# PCB_Telemetria_2020.net
KiCad netlist of a schematic drawn in EAGLE
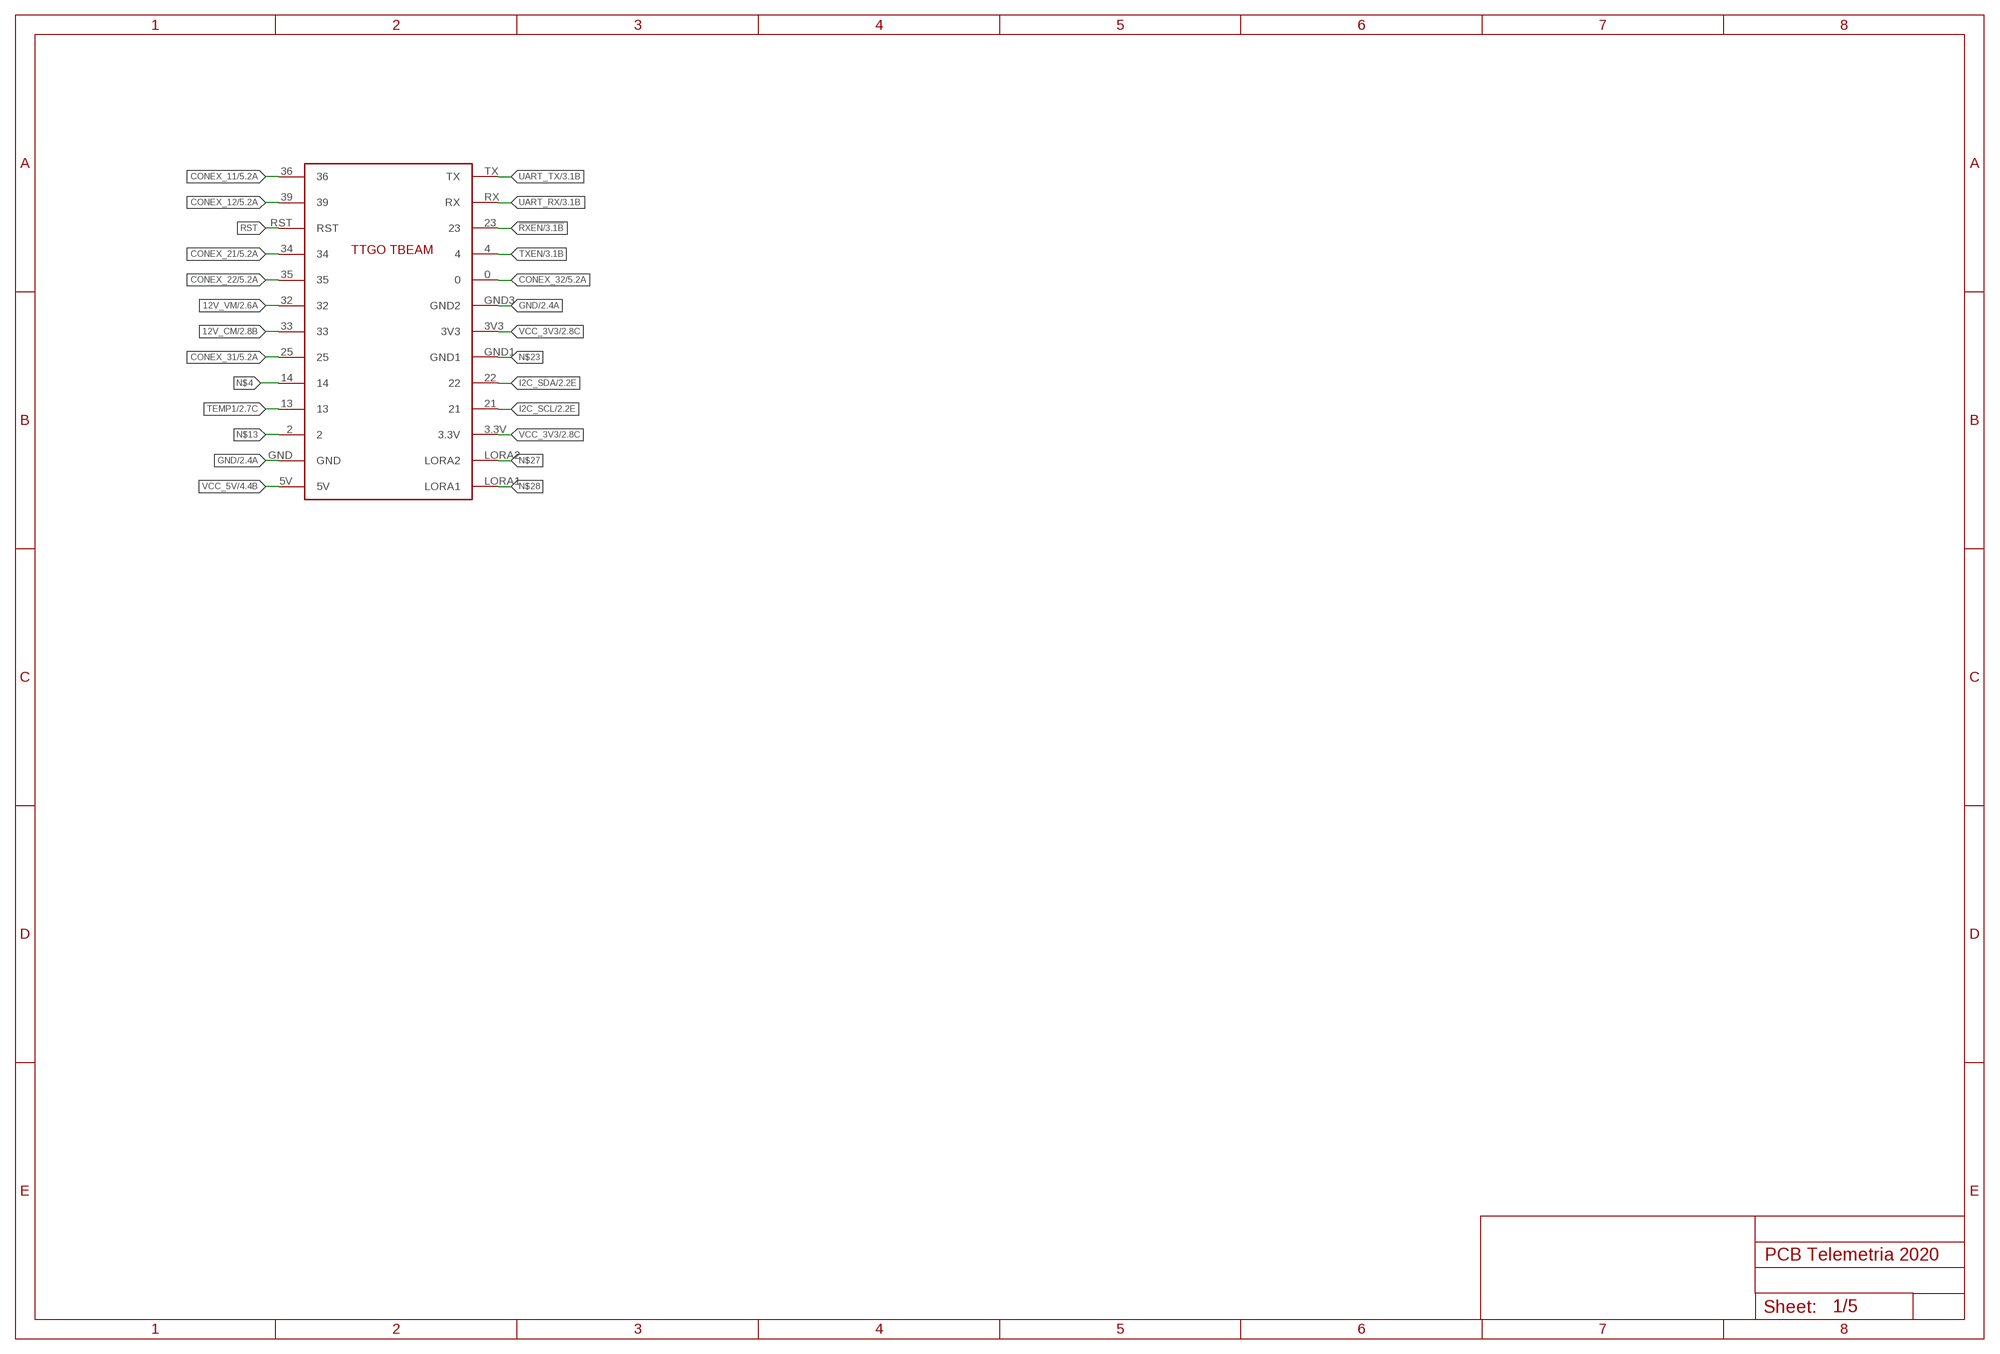
[diagram p0: schematic, sheet 1]
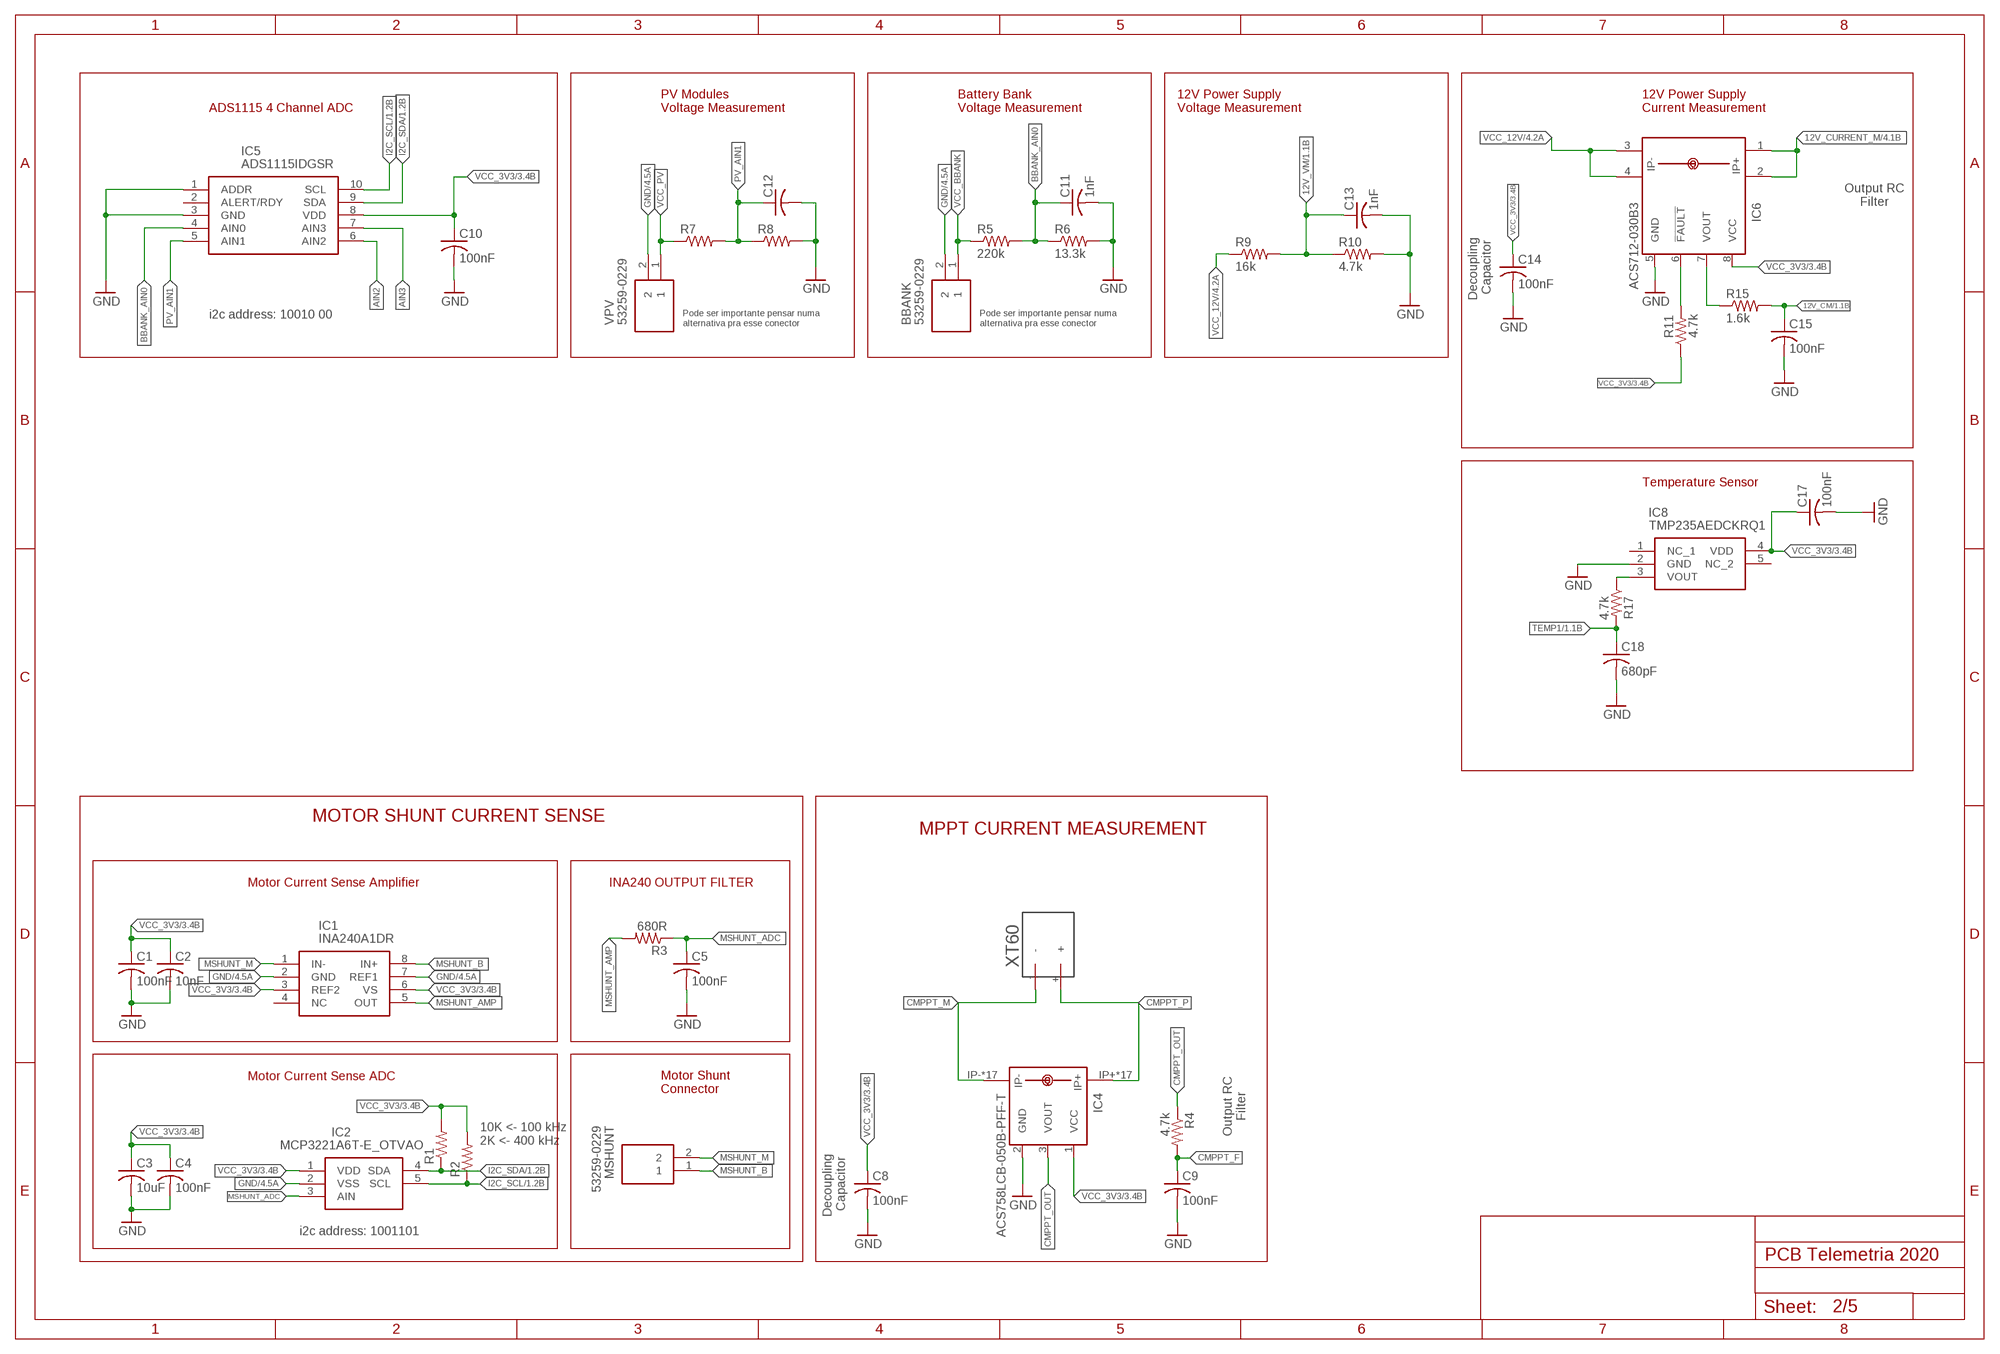
[diagram p1: schematic, sheet 2]
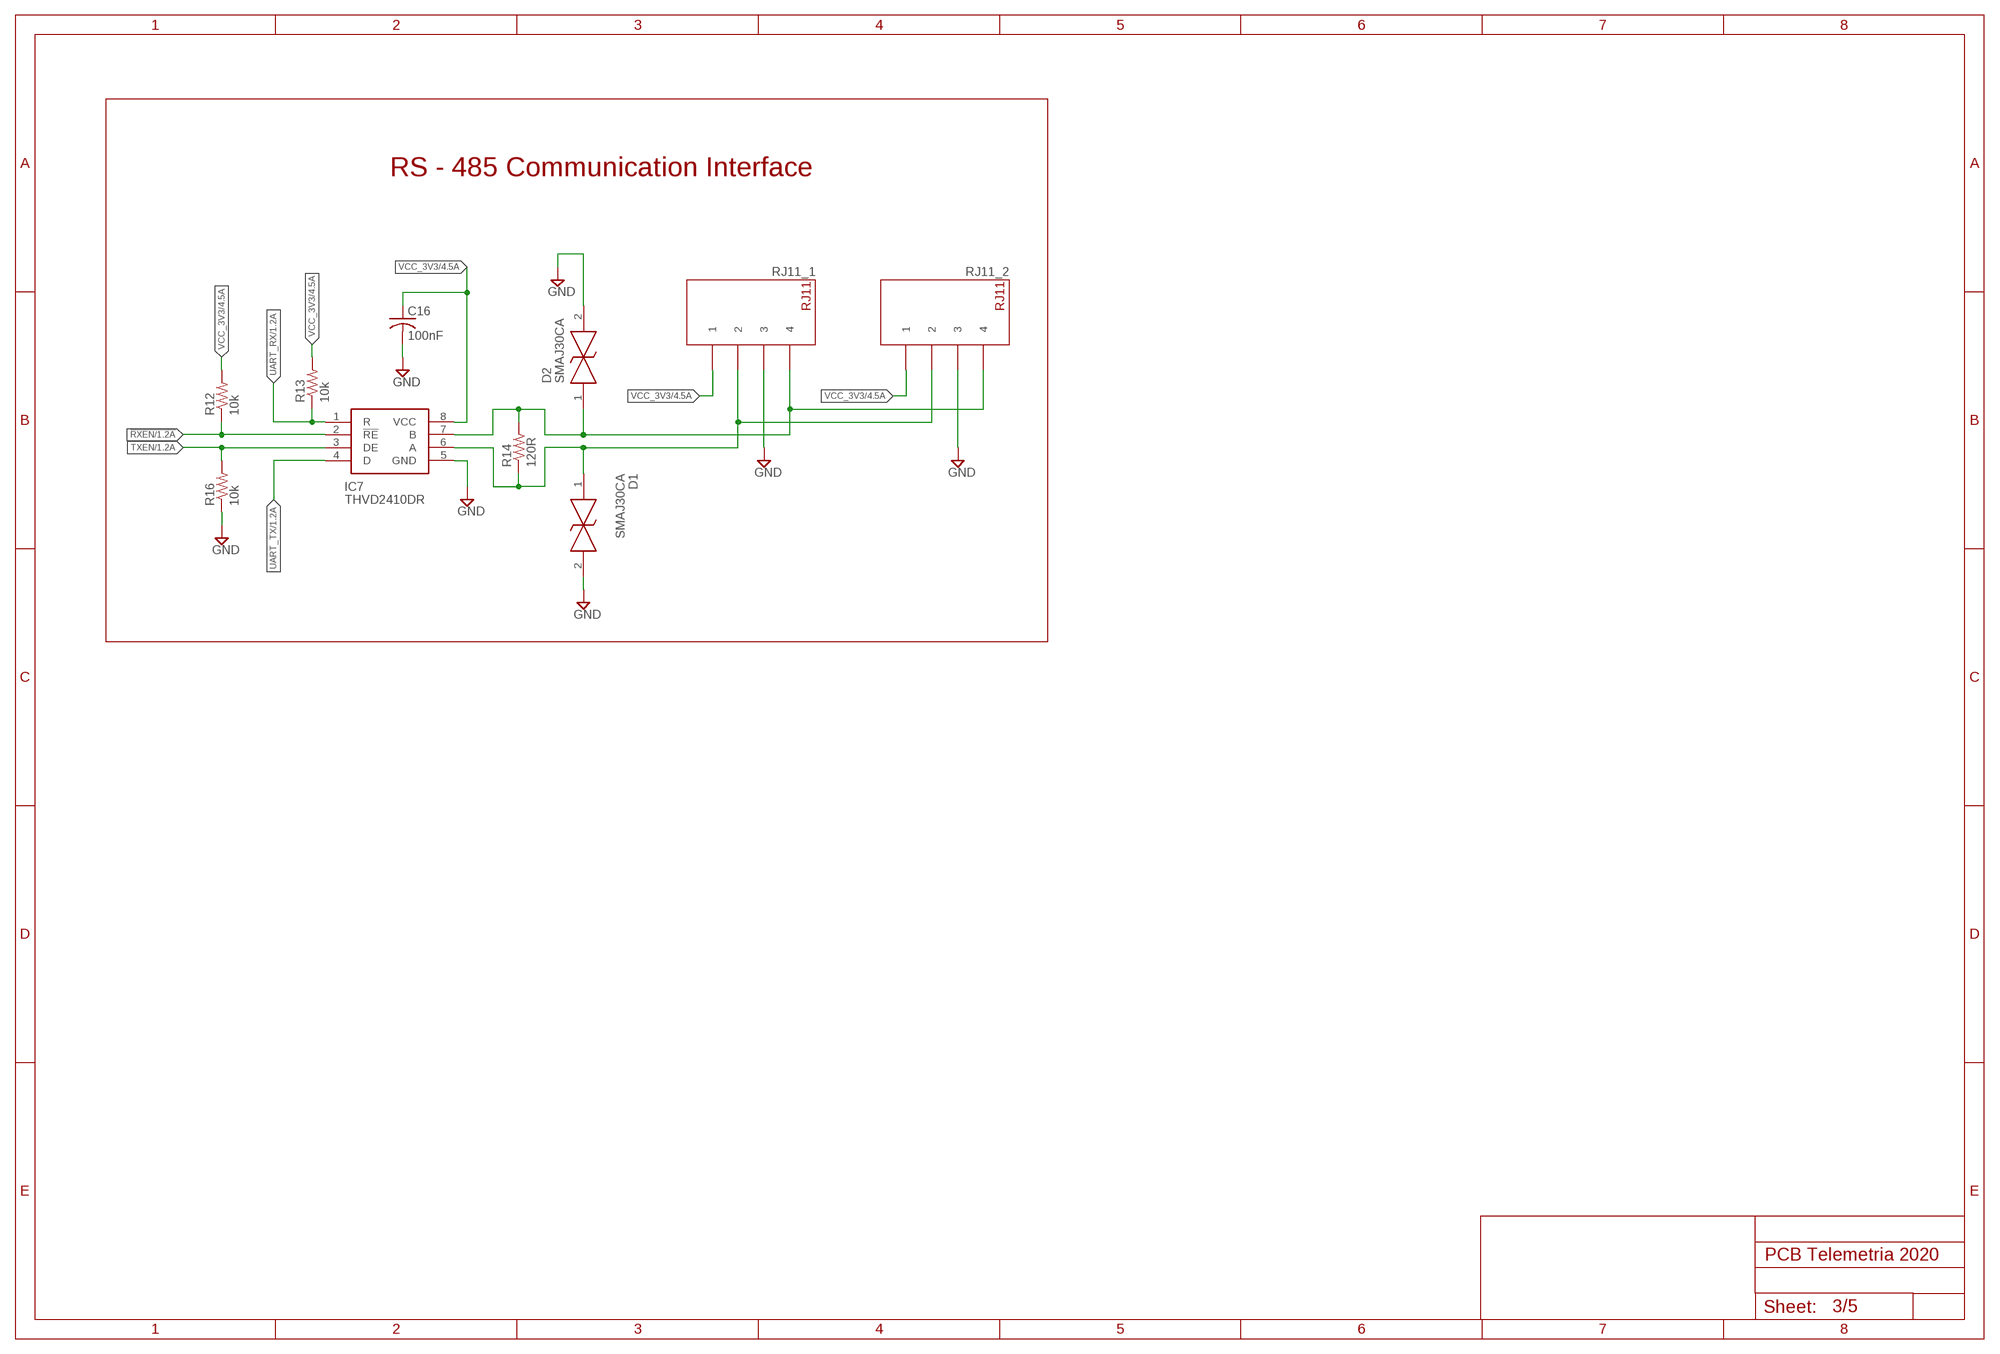
[diagram p2: schematic, sheet 3]
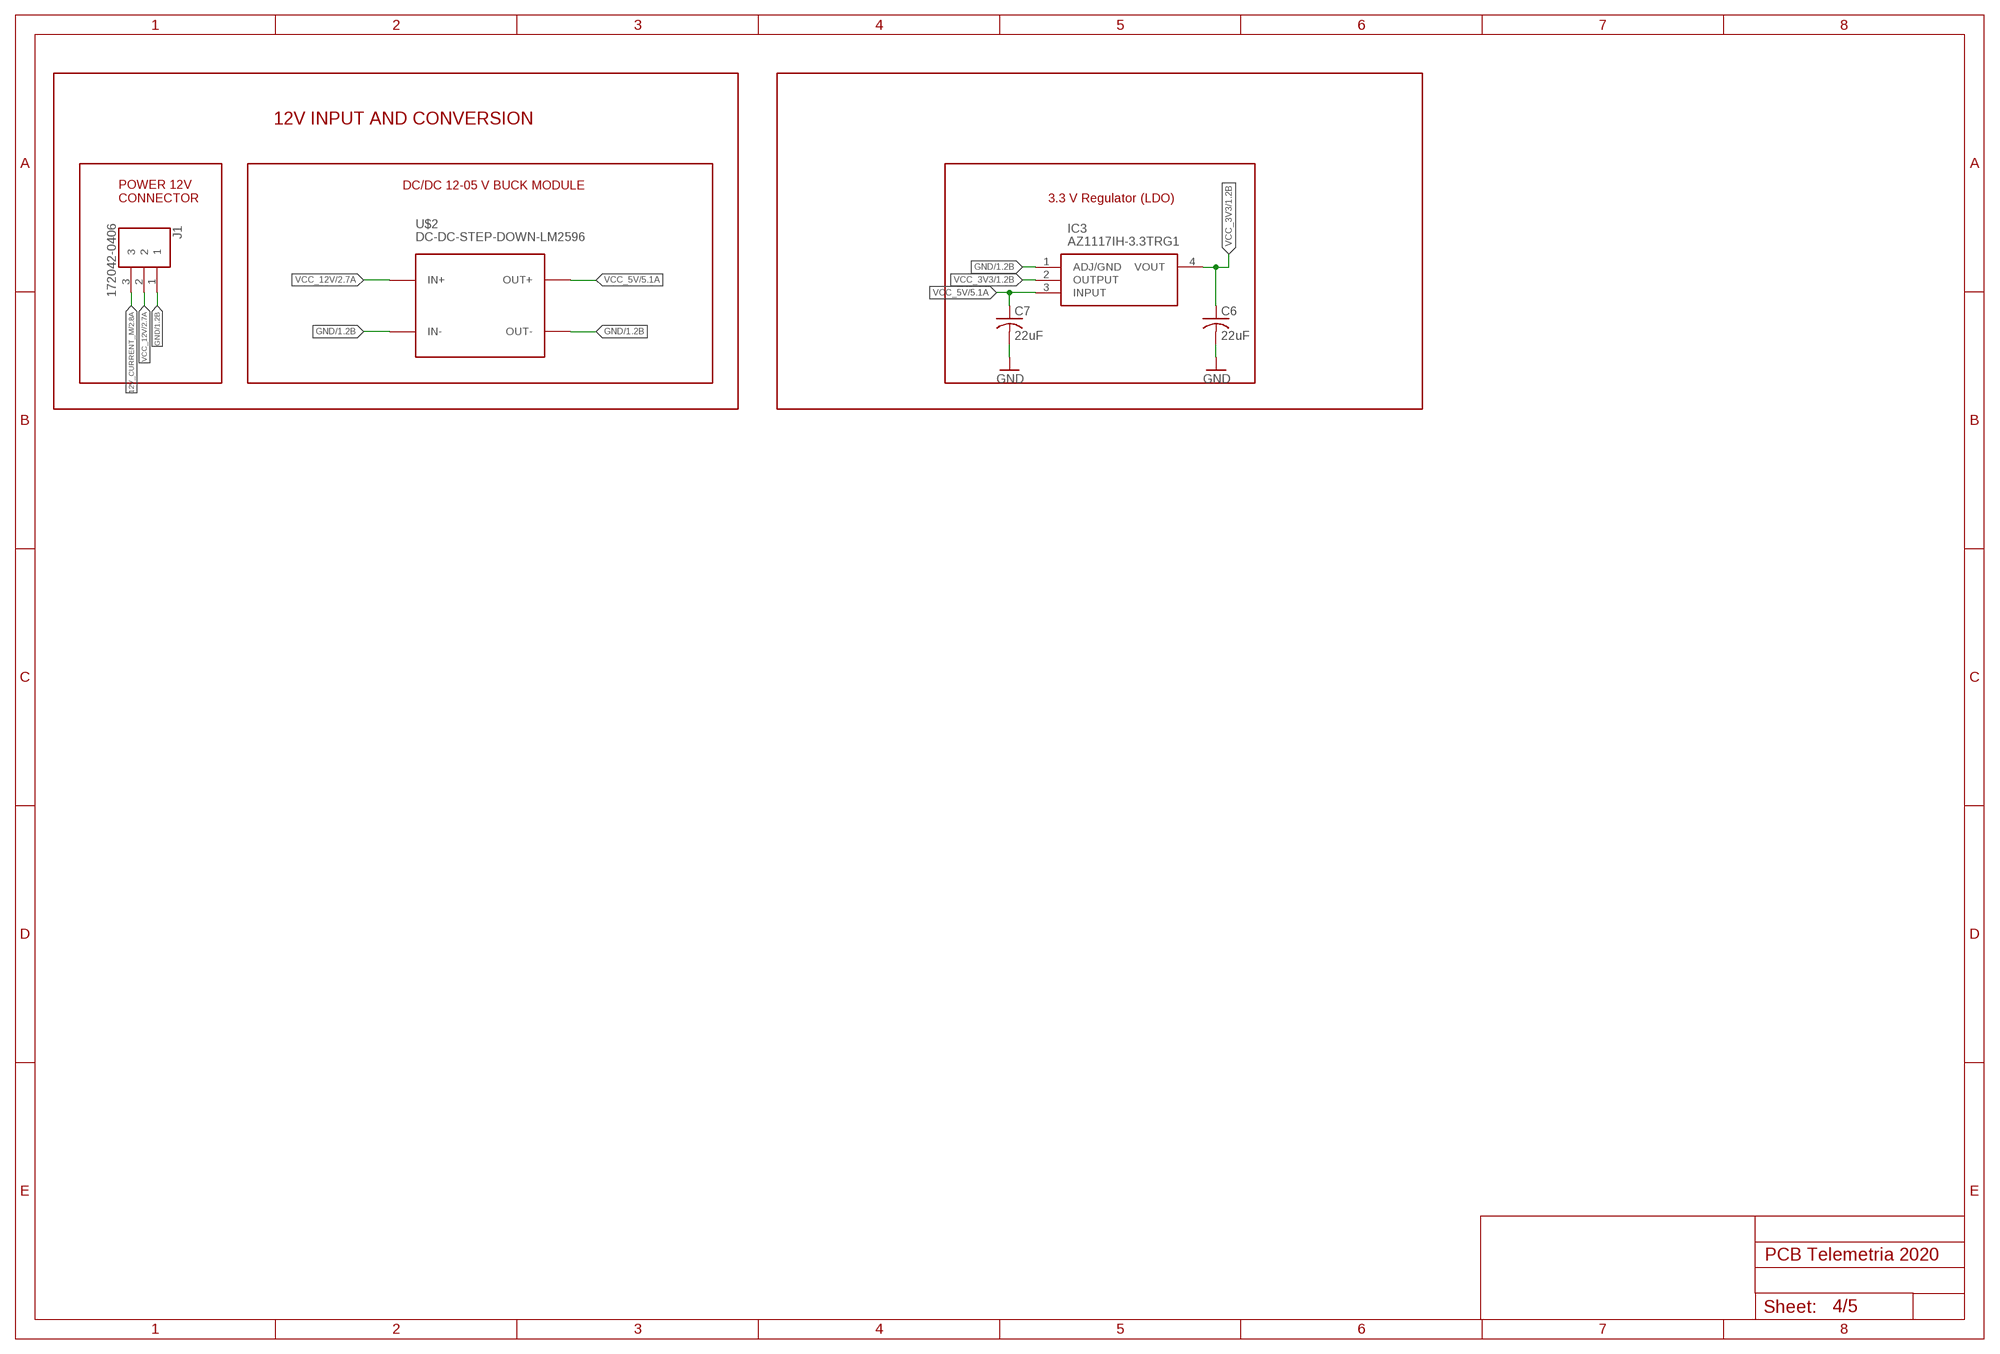
[diagram p3: schematic, sheet 4]
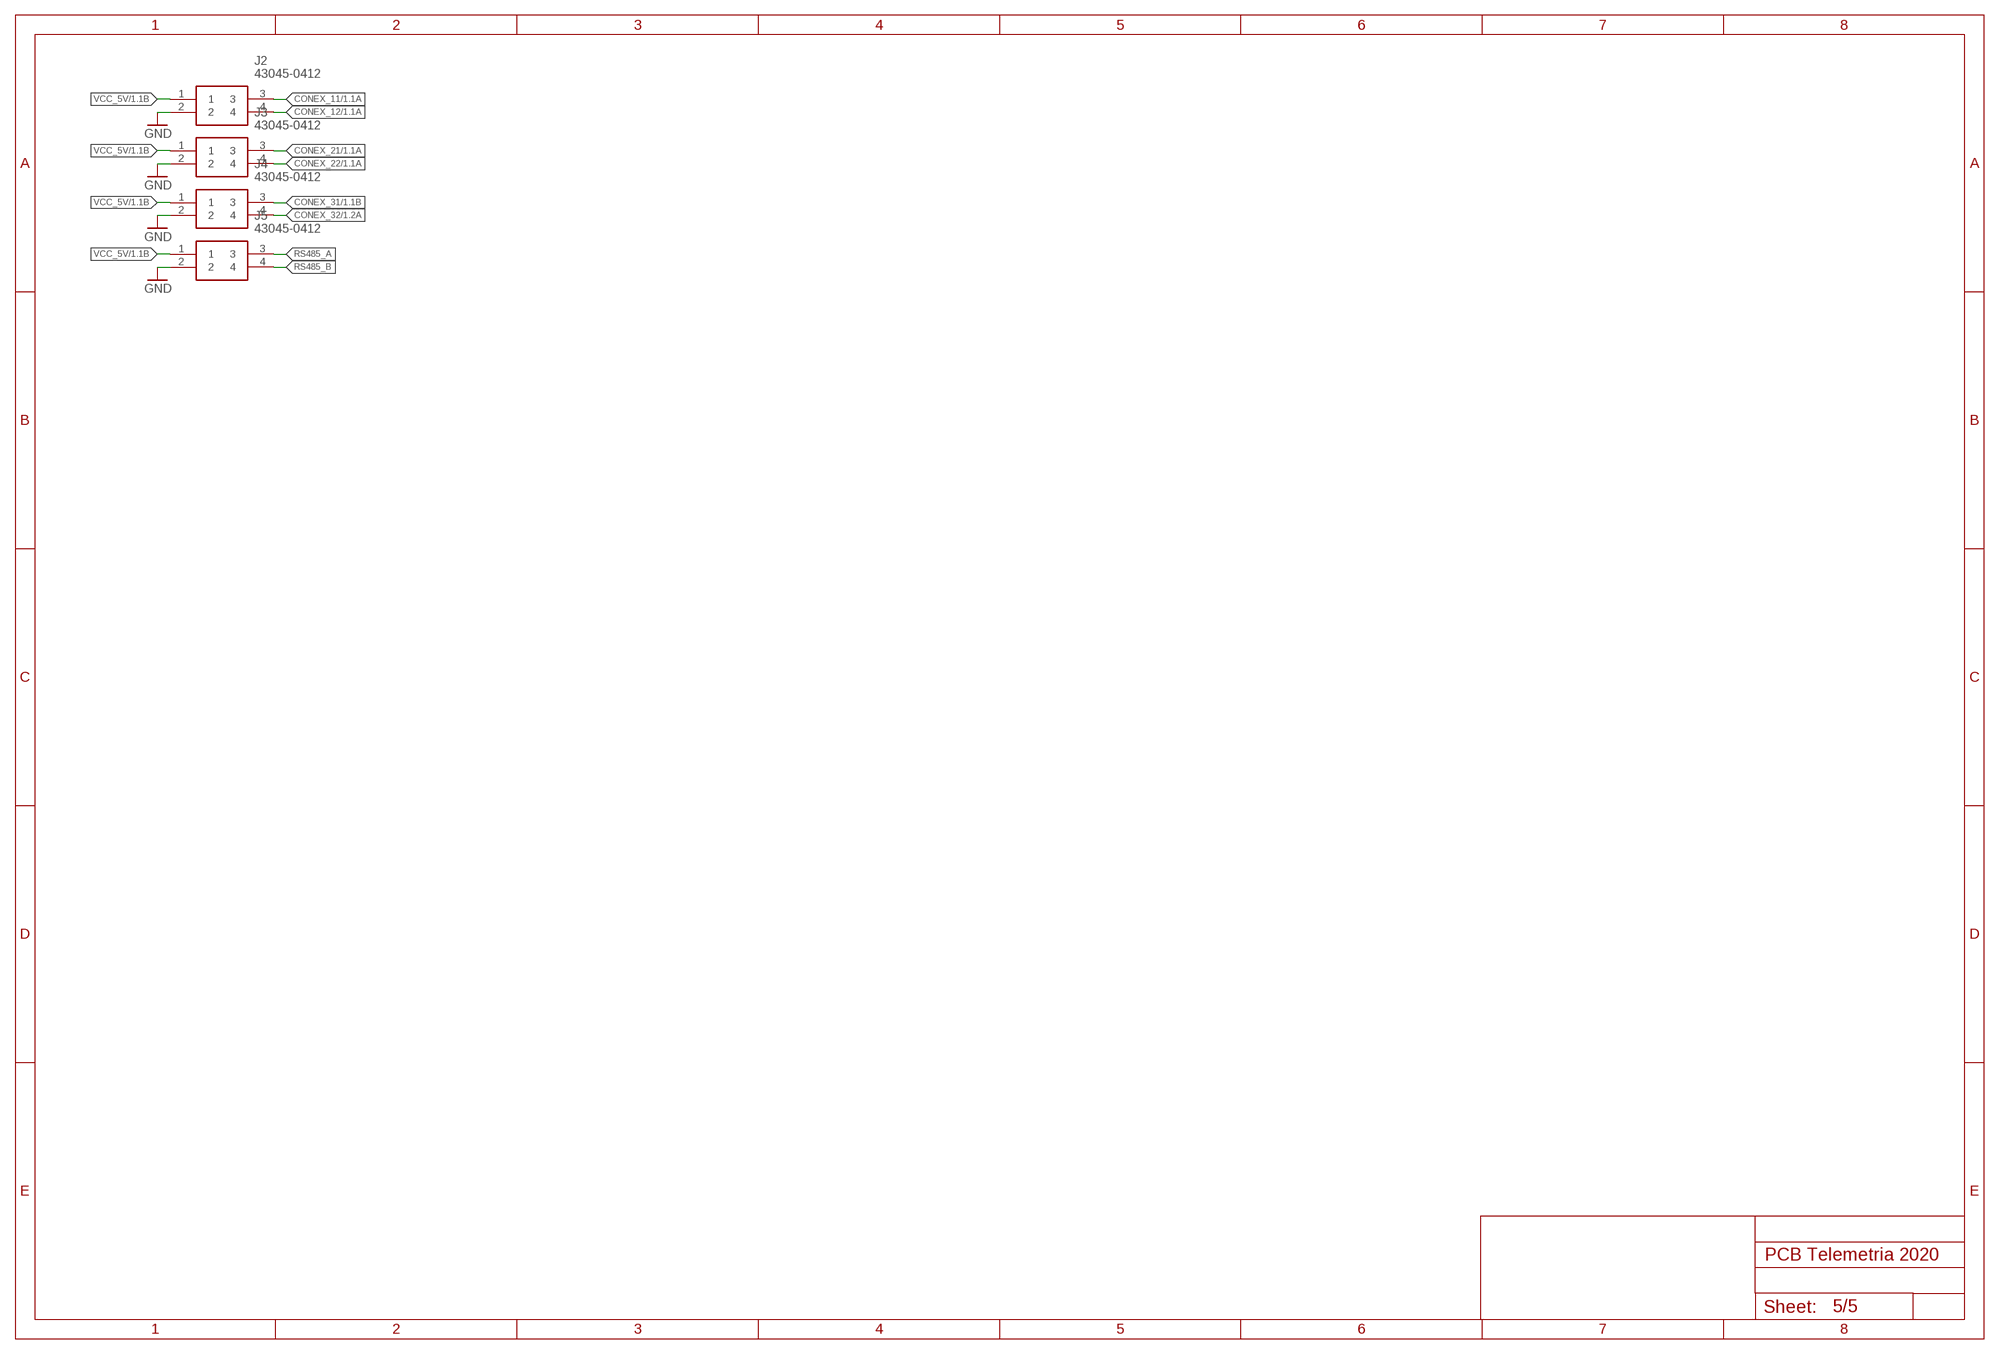
[diagram p4: schematic, sheet 5]

(export (version "E")
  (design (tool "Eeschema 10.0.6"))
  (components
    (comp (ref "C6")
      (value "22uF")
      (footprint "eagle-import:C0805")
      (libsource (lib "eagle-import") (part "C-USC0805"))
    )
    (comp (ref "C7")
      (value "22uF")
      (footprint "eagle-import:C0805")
      (libsource (lib "eagle-import") (part "C-USC0805"))
    )
    (comp (ref "IC3")
      (value "AZ1117IH-3.3TRG1")
      (footprint "eagle-import:SOT230P700X170-4N")
      (fields (field (name "MOUSER_PART_NUMBER") "621-AZ1117IH-3.3TRG1"))
      (libsource (lib "eagle-import") (part "AZ1117IH-3.3TRG1"))
    )
    (comp (ref "J1")
      (value "172042-0406")
      (footprint "eagle-import:MOLEX_172042-0406")
      (fields (field (name "MF") "Molex") (field (name "MP") "172042-0302"))
      (libsource (lib "eagle-import") (part "172042-0406"))
    )
    (comp (ref "U$2")
      (value "DC-DC-STEP-DOWN-LM2596")
      (footprint "eagle-import:DC-DC-STEP-DOWN-LM2596")
      (libsource (lib "eagle-import") (part "DC-DC-STEP-DOWN-LM2596"))
    )
    (comp (ref "U$1")
      (value "TTGOBEAM")
      (footprint "eagle-import:TTGOBEAM")
      (libsource (lib "eagle-import") (part "TTGOBEAM"))
    )
    (comp (ref "C16")
      (value "100nF")
      (footprint "eagle-import:C0805")
      (libsource (lib "eagle-import") (part "C-USC0805"))
    )
    (comp (ref "D1")
      (value "SMAJ30CA")
      (footprint "eagle-import:DIONM5026X229N")
      (fields (field (name "MOUSER_PART_NUMBER") "576-SMAJ30CA"))
      (libsource (lib "eagle-import") (part "SMAJ30CA"))
    )
    (comp (ref "D2")
      (value "SMAJ30CA")
      (footprint "eagle-import:DIONM5026X229N")
      (fields (field (name "MOUSER_PART_NUMBER") "576-SMAJ30CA"))
      (libsource (lib "eagle-import") (part "SMAJ30CA"))
    )
    (comp (ref "IC7")
      (value "THVD2410DR")
      (footprint "eagle-import:SOIC127P600X175-8N")
      (fields (field (name "MOUSER_PART_NUMBER") "595-THVD2410DR"))
      (libsource (lib "eagle-import") (part "THVD2410DR"))
    )
    (comp (ref "R12")
      (value "10k")
      (footprint "eagle-import:M0805")
      (libsource (lib "eagle-import") (part "R-US_M0805"))
    )
    (comp (ref "R13")
      (value "10k")
      (footprint "eagle-import:M0805")
      (libsource (lib "eagle-import") (part "R-US_M0805"))
    )
    (comp (ref "R14")
      (value "120R")
      (footprint "eagle-import:M0805")
      (libsource (lib "eagle-import") (part "R-US_M0805"))
    )
    (comp (ref "R16")
      (value "10k")
      (footprint "eagle-import:M0805")
      (libsource (lib "eagle-import") (part "R-US_M0805"))
    )
    (comp (ref "RJ11_1")
      (value "TFC44")
      (footprint "eagle-import:TFC44")
      (libsource (lib "eagle-import") (part "TFC44"))
    )
    (comp (ref "RJ11_2")
      (value "TFC44")
      (footprint "eagle-import:TFC44")
      (libsource (lib "eagle-import") (part "TFC44"))
    )
    (comp (ref "J2")
      (value "43045-0412")
      (footprint "eagle-import:43045-0412")
      (fields (field (name "MOUSER_PART_NUMBER") "538-43045-0412"))
      (libsource (lib "eagle-import") (part "43045-0412"))
    )
    (comp (ref "J3")
      (value "43045-0412")
      (footprint "eagle-import:43045-0412")
      (fields (field (name "MOUSER_PART_NUMBER") "538-43045-0412"))
      (libsource (lib "eagle-import") (part "43045-0412"))
    )
    (comp (ref "J4")
      (value "43045-0412")
      (footprint "eagle-import:43045-0412")
      (fields (field (name "MOUSER_PART_NUMBER") "538-43045-0412"))
      (libsource (lib "eagle-import") (part "43045-0412"))
    )
    (comp (ref "J5")
      (value "43045-0412")
      (footprint "eagle-import:43045-0412")
      (fields (field (name "MOUSER_PART_NUMBER") "538-43045-0412"))
      (libsource (lib "eagle-import") (part "43045-0412"))
    )
    (comp (ref "BBANK")
      (value "53259-0229")
      (footprint "eagle-import:0532590229")
      (fields (field (name "MOUSER_PART_NUMBER") "538-53259-0229"))
      (libsource (lib "eagle-import") (part "53259-0229"))
    )
    (comp (ref "C1")
      (value "100nF")
      (footprint "eagle-import:C0805")
      (libsource (lib "eagle-import") (part "C-USC0805"))
    )
    (comp (ref "C2")
      (value "10nF")
      (footprint "eagle-import:C0805")
      (libsource (lib "eagle-import") (part "C-USC0805"))
    )
    (comp (ref "C3")
      (value "10uF")
      (footprint "eagle-import:C0805")
      (libsource (lib "eagle-import") (part "C-USC0805"))
    )
    (comp (ref "C4")
      (value "100nF")
      (footprint "eagle-import:C0805")
      (libsource (lib "eagle-import") (part "C-USC0805"))
    )
    (comp (ref "C5")
      (value "100nF")
      (footprint "eagle-import:C0805")
      (libsource (lib "eagle-import") (part "C-USC0805"))
    )
    (comp (ref "C8")
      (value "100nF")
      (footprint "eagle-import:C0805")
      (libsource (lib "eagle-import") (part "C-USC0805"))
    )
    (comp (ref "C9")
      (value "100nF")
      (footprint "eagle-import:C0805")
      (libsource (lib "eagle-import") (part "C-USC0805"))
    )
    (comp (ref "C10")
      (value "100nF")
      (footprint "eagle-import:C0805")
      (libsource (lib "eagle-import") (part "C-USC0805"))
    )
    (comp (ref "C11")
      (value "1nF")
      (footprint "eagle-import:C0805")
      (libsource (lib "eagle-import") (part "C-USC0805"))
    )
    (comp (ref "C12")
      (value "C-USC0805")
      (footprint "eagle-import:C0805")
      (libsource (lib "eagle-import") (part "C-USC0805"))
    )
    (comp (ref "C13")
      (value "1nF")
      (footprint "eagle-import:C0805")
      (libsource (lib "eagle-import") (part "C-USC0805"))
    )
    (comp (ref "C14")
      (value "100nF")
      (footprint "eagle-import:C0805")
      (libsource (lib "eagle-import") (part "C-USC0805"))
    )
    (comp (ref "C15")
      (value "100nF")
      (footprint "eagle-import:C0805")
      (libsource (lib "eagle-import") (part "C-USC0805"))
    )
    (comp (ref "C17")
      (value "100nF")
      (footprint "eagle-import:C0805")
      (libsource (lib "eagle-import") (part "C-USC0805"))
    )
    (comp (ref "C18")
      (value "680pF")
      (footprint "eagle-import:C0805")
      (libsource (lib "eagle-import") (part "C-USC0805"))
    )
    (comp (ref "IC1")
      (value "INA240A1DR")
      (footprint "eagle-import:SOIC127P600X175-8N")
      (fields (field (name "MOUSER_PART_NUMBER") "595-INA240A1DR"))
      (libsource (lib "eagle-import") (part "INA240A1DR"))
    )
    (comp (ref "IC2")
      (value "MCP3221A6T-E_OTVAO")
      (footprint "eagle-import:SOT95P280X145-5N")
      (fields
        (field (name "MANUFACTURER_PART_NUMBER") "MCP3221A6T-E/OTVAO")
        (field (name "MOUSER_PART_NUMBER") "579-MCP3221A6TEOTVAO")
      )
      (libsource (lib "eagle-import") (part "MCP3221A6T-E_OTVAO"))
    )
    (comp (ref "IC4")
      (value "ACS758LCB-050B-PFF-T")
      (footprint "eagle-import:CB-PFF")
      (libsource (lib "eagle-import") (part "ACS758LCB-050B-PFF-T"))
    )
    (comp (ref "IC5")
      (value "ADS1115IDGSR")
      (footprint "eagle-import:SOP50P490X110-10N")
      (fields (field (name "MOUSER_PART_NUMBER") "595-ADS1115IDGSR"))
      (libsource (lib "eagle-import") (part "ADS1115IDGSR"))
    )
    (comp (ref "IC6")
      (value "ACS712-030B3")
      (footprint "eagle-import:SOIC8")
      (libsource (lib "eagle-import") (part "ACS712-LC"))
    )
    (comp (ref "IC8")
      (value "TMP235AEDCKRQ1")
      (footprint "eagle-import:SOT65P210X110-5N")
      (fields (field (name "MOUSER_PART_NUMBER") "595-TMP235AEDCKRQ1"))
      (libsource (lib "eagle-import") (part "TMP235AEDCKRQ1"))
    )
    (comp (ref "MSHUNT")
      (value "53259-0229")
      (footprint "eagle-import:0532590229")
      (fields (field (name "MOUSER_PART_NUMBER") "538-53259-0229"))
      (libsource (lib "eagle-import") (part "53259-0229"))
    )
    (comp (ref "R1")
      (value "R-US_R0805")
      (footprint "eagle-import:R0805")
      (libsource (lib "eagle-import") (part "R-US_R0805"))
    )
    (comp (ref "R2")
      (value "R-US_R0805")
      (footprint "eagle-import:R0805")
      (libsource (lib "eagle-import") (part "R-US_R0805"))
    )
    (comp (ref "R3")
      (value "680R")
      (footprint "eagle-import:R0805")
      (libsource (lib "eagle-import") (part "R-US_R0805"))
    )
    (comp (ref "R4")
      (value "4.7k")
      (footprint "eagle-import:R0805")
      (libsource (lib "eagle-import") (part "R-US_R0805"))
    )
    (comp (ref "R5")
      (value "220k")
      (footprint "eagle-import:R0805")
      (libsource (lib "eagle-import") (part "R-US_R0805"))
    )
    (comp (ref "R6")
      (value "13.3k")
      (footprint "eagle-import:R0805")
      (libsource (lib "eagle-import") (part "R-US_R0805"))
    )
    (comp (ref "R7")
      (value "R-US_R0805")
      (footprint "eagle-import:R0805")
      (libsource (lib "eagle-import") (part "R-US_R0805"))
    )
    (comp (ref "R8")
      (value "R-US_R0805")
      (footprint "eagle-import:R0805")
      (libsource (lib "eagle-import") (part "R-US_R0805"))
    )
    (comp (ref "R9")
      (value "16k")
      (footprint "eagle-import:R0805")
      (libsource (lib "eagle-import") (part "R-US_R0805"))
    )
    (comp (ref "R10")
      (value "4.7k")
      (footprint "eagle-import:R0805")
      (libsource (lib "eagle-import") (part "R-US_R0805"))
    )
    (comp (ref "R11")
      (value "4.7k")
      (footprint "eagle-import:R0805")
      (libsource (lib "eagle-import") (part "R-US_R0805"))
    )
    (comp (ref "R15")
      (value "1.6k")
      (footprint "eagle-import:R0805")
      (libsource (lib "eagle-import") (part "R-US_R0805"))
    )
    (comp (ref "R17")
      (value "4.7k")
      (footprint "eagle-import:R0805")
      (libsource (lib "eagle-import") (part "R-US_R0805"))
    )
    (comp (ref "U$3")
      (value "XT60")
      (footprint "eagle-import:XT60")
      (libsource (lib "eagle-import") (part "XT60"))
    )
    (comp (ref "VPV")
      (value "53259-0229")
      (footprint "eagle-import:0532590229")
      (fields (field (name "MOUSER_PART_NUMBER") "538-53259-0229"))
      (libsource (lib "eagle-import") (part "53259-0229"))
    )
  )
  (nets
    (net (code "1") (name "12V_CM") (class "Default")
      (node (ref "C15") (pin "1") (pinfunction "1_1") (pintype "passive"))
      (node (ref "R15") (pin "2") (pinfunction "2_2") (pintype "passive"))
      (node (ref "U$1") (pin "33") (pinfunction "33_33") (pintype "bidirectional"))
    )
    (net (code "2") (name "12V_CURRENT_M") (class "Default")
      (node (ref "IC6") (pin "1") (pinfunction "IP+_1") (pintype "passive"))
      (node (ref "IC6") (pin "2") (pinfunction "IP+1_2") (pintype "passive"))
      (node (ref "J1") (pin "3") (pinfunction "3_3") (pintype "passive"))
    )
    (net (code "3") (name "12V_VM") (class "Default")
      (node (ref "C13") (pin "1") (pinfunction "1_1") (pintype "passive"))
      (node (ref "R10") (pin "1") (pinfunction "1_1") (pintype "passive"))
      (node (ref "R9") (pin "2") (pinfunction "2_2") (pintype "passive"))
      (node (ref "U$1") (pin "32") (pinfunction "32_32") (pintype "bidirectional"))
    )
    (net (code "4") (name "AIN2") (class "Default")
      (node (ref "IC5") (pin "6") (pinfunction "AIN2_6") (pintype "bidirectional"))
    )
    (net (code "5") (name "AIN3") (class "Default")
      (node (ref "IC5") (pin "7") (pinfunction "AIN3_7") (pintype "bidirectional"))
    )
    (net (code "6") (name "BBANK_AIN0") (class "Default")
      (node (ref "C11") (pin "1") (pinfunction "1_1") (pintype "passive"))
      (node (ref "IC5") (pin "4") (pinfunction "AIN0_4") (pintype "bidirectional"))
      (node (ref "R5") (pin "2") (pinfunction "2_2") (pintype "passive"))
      (node (ref "R6") (pin "1") (pinfunction "1_1") (pintype "passive"))
    )
    (net (code "7") (name "CMPPT_F") (class "Default")
      (node (ref "C9") (pin "1") (pinfunction "1_1") (pintype "passive"))
      (node (ref "R4") (pin "2") (pinfunction "2_2") (pintype "passive"))
    )
    (net (code "8") (name "CMPPT_M") (class "Default")
      (node (ref "IC4") (pin "IP-") (pinfunction "IP-_IP-") (pintype "passive"))
      (node (ref "IC4") (pin "IP-@10") (pinfunction "IP-_IP-@10") (pintype "passive"))
      (node (ref "IC4") (pin "IP-@11") (pinfunction "IP-_IP-@11") (pintype "passive"))
      (node (ref "IC4") (pin "IP-@12") (pinfunction "IP-_IP-@12") (pintype "passive"))
      (node (ref "IC4") (pin "IP-@13") (pinfunction "IP-_IP-@13") (pintype "passive"))
      (node (ref "IC4") (pin "IP-@14") (pinfunction "IP-_IP-@14") (pintype "passive"))
      (node (ref "IC4") (pin "IP-@15") (pinfunction "IP-_IP-@15") (pintype "passive"))
      (node (ref "IC4") (pin "IP-@16") (pinfunction "IP-_IP-@16") (pintype "passive"))
      (node (ref "IC4") (pin "IP-@17") (pinfunction "IP-_IP-@17") (pintype "passive"))
      (node (ref "IC4") (pin "IP-@2") (pinfunction "IP-_IP-@2") (pintype "passive"))
      (node (ref "IC4") (pin "IP-@3") (pinfunction "IP-_IP-@3") (pintype "passive"))
      (node (ref "IC4") (pin "IP-@4") (pinfunction "IP-_IP-@4") (pintype "passive"))
      (node (ref "IC4") (pin "IP-@5") (pinfunction "IP-_IP-@5") (pintype "passive"))
      (node (ref "IC4") (pin "IP-@6") (pinfunction "IP-_IP-@6") (pintype "passive"))
      (node (ref "IC4") (pin "IP-@7") (pinfunction "IP-_IP-@7") (pintype "passive"))
      (node (ref "IC4") (pin "IP-@8") (pinfunction "IP-_IP-@8") (pintype "passive"))
      (node (ref "IC4") (pin "IP-@9") (pinfunction "IP-_IP-@9") (pintype "passive"))
      (node (ref "U$3") (pin "-") (pinfunction "-_-") (pintype "bidirectional"))
    )
    (net (code "9") (name "CMPPT_OUT") (class "Default")
      (node (ref "IC4") (pin "3") (pinfunction "VOUT_3") (pintype "output"))
      (node (ref "R4") (pin "1") (pinfunction "1_1") (pintype "passive"))
    )
    (net (code "10") (name "CMPPT_P") (class "Default")
      (node (ref "IC4") (pin "IP+") (pinfunction "IP+_IP+") (pintype "passive"))
      (node (ref "IC4") (pin "IP+@10") (pinfunction "IP+_IP+@10") (pintype "passive"))
      (node (ref "IC4") (pin "IP+@11") (pinfunction "IP+_IP+@11") (pintype "passive"))
      (node (ref "IC4") (pin "IP+@12") (pinfunction "IP+_IP+@12") (pintype "passive"))
      (node (ref "IC4") (pin "IP+@13") (pinfunction "IP+_IP+@13") (pintype "passive"))
      (node (ref "IC4") (pin "IP+@14") (pinfunction "IP+_IP+@14") (pintype "passive"))
      (node (ref "IC4") (pin "IP+@15") (pinfunction "IP+_IP+@15") (pintype "passive"))
      (node (ref "IC4") (pin "IP+@16") (pinfunction "IP+_IP+@16") (pintype "passive"))
      (node (ref "IC4") (pin "IP+@17") (pinfunction "IP+_IP+@17") (pintype "passive"))
      (node (ref "IC4") (pin "IP+@2") (pinfunction "IP+_IP+@2") (pintype "passive"))
      (node (ref "IC4") (pin "IP+@3") (pinfunction "IP+_IP+@3") (pintype "passive"))
      (node (ref "IC4") (pin "IP+@4") (pinfunction "IP+_IP+@4") (pintype "passive"))
      (node (ref "IC4") (pin "IP+@5") (pinfunction "IP+_IP+@5") (pintype "passive"))
      (node (ref "IC4") (pin "IP+@6") (pinfunction "IP+_IP+@6") (pintype "passive"))
      (node (ref "IC4") (pin "IP+@7") (pinfunction "IP+_IP+@7") (pintype "passive"))
      (node (ref "IC4") (pin "IP+@8") (pinfunction "IP+_IP+@8") (pintype "passive"))
      (node (ref "IC4") (pin "IP+@9") (pinfunction "IP+_IP+@9") (pintype "passive"))
      (node (ref "U$3") (pin "+") (pinfunction "+_+") (pintype "bidirectional"))
    )
    (net (code "11") (name "CONEX_11") (class "Default")
      (node (ref "J2") (pin "3") (pinfunction "3_3") (pintype "bidirectional"))
      (node (ref "U$1") (pin "36") (pinfunction "36_36") (pintype "bidirectional"))
    )
    (net (code "12") (name "CONEX_12") (class "Default")
      (node (ref "J2") (pin "4") (pinfunction "4_4") (pintype "bidirectional"))
      (node (ref "U$1") (pin "39") (pinfunction "39_39") (pintype "bidirectional"))
    )
    (net (code "13") (name "CONEX_21") (class "Default")
      (node (ref "J3") (pin "3") (pinfunction "3_3") (pintype "bidirectional"))
      (node (ref "U$1") (pin "34") (pinfunction "34_34") (pintype "bidirectional"))
    )
    (net (code "14") (name "CONEX_22") (class "Default")
      (node (ref "J3") (pin "4") (pinfunction "4_4") (pintype "bidirectional"))
      (node (ref "U$1") (pin "35") (pinfunction "35_35") (pintype "bidirectional"))
    )
    (net (code "15") (name "CONEX_31") (class "Default")
      (node (ref "J4") (pin "3") (pinfunction "3_3") (pintype "bidirectional"))
      (node (ref "U$1") (pin "25") (pinfunction "25_25") (pintype "bidirectional"))
    )
    (net (code "16") (name "CONEX_32") (class "Default")
      (node (ref "J4") (pin "4") (pinfunction "4_4") (pintype "bidirectional"))
      (node (ref "U$1") (pin "0") (pinfunction "0_0") (pintype "bidirectional"))
    )
    (net (code "17") (name "GND") (class "Default")
      (node (ref "BBANK") (pin "2") (pinfunction "2_2") (pintype "bidirectional"))
      (node (ref "C1") (pin "2") (pinfunction "2_2") (pintype "passive"))
      (node (ref "C10") (pin "2") (pinfunction "2_2") (pintype "passive"))
      (node (ref "C11") (pin "2") (pinfunction "2_2") (pintype "passive"))
      (node (ref "C12") (pin "2") (pinfunction "2_2") (pintype "passive"))
      (node (ref "C13") (pin "2") (pinfunction "2_2") (pintype "passive"))
      (node (ref "C14") (pin "2") (pinfunction "2_2") (pintype "passive"))
      (node (ref "C15") (pin "2") (pinfunction "2_2") (pintype "passive"))
      (node (ref "C16") (pin "2") (pinfunction "2_2") (pintype "passive"))
      (node (ref "C17") (pin "2") (pinfunction "2_2") (pintype "passive"))
      (node (ref "C18") (pin "2") (pinfunction "2_2") (pintype "passive"))
      (node (ref "C2") (pin "2") (pinfunction "2_2") (pintype "passive"))
      (node (ref "C3") (pin "2") (pinfunction "2_2") (pintype "passive"))
      (node (ref "C4") (pin "2") (pinfunction "2_2") (pintype "passive"))
      (node (ref "C5") (pin "2") (pinfunction "2_2") (pintype "passive"))
      (node (ref "C6") (pin "2") (pinfunction "2_2") (pintype "passive"))
      (node (ref "C7") (pin "2") (pinfunction "2_2") (pintype "passive"))
      (node (ref "C8") (pin "2") (pinfunction "2_2") (pintype "passive"))
      (node (ref "C9") (pin "2") (pinfunction "2_2") (pintype "passive"))
      (node (ref "D1") (pin "2") (pinfunction "2_2") (pintype "bidirectional"))
      (node (ref "D2") (pin "2") (pinfunction "2_2") (pintype "bidirectional"))
      (node (ref "IC1") (pin "2") (pinfunction "GND_2") (pintype "bidirectional"))
      (node (ref "IC1") (pin "7") (pinfunction "REF1_7") (pintype "bidirectional"))
      (node (ref "IC2") (pin "2") (pinfunction "VSS_2") (pintype "bidirectional"))
      (node (ref "IC3") (pin "1") (pinfunction "ADJ/GND_1") (pintype "bidirectional"))
      (node (ref "IC4") (pin "2") (pinfunction "GND_2") (pintype "power_in"))
      (node (ref "IC5") (pin "1") (pinfunction "ADDR_1") (pintype "bidirectional"))
      (node (ref "IC5") (pin "3") (pinfunction "GND_3") (pintype "bidirectional"))
      (node (ref "IC6") (pin "5") (pinfunction "GND_5") (pintype "power_in"))
      (node (ref "IC7") (pin "5") (pinfunction "GND_5") (pintype "bidirectional"))
      (node (ref "IC8") (pin "2") (pinfunction "GND_2") (pintype "bidirectional"))
      (node (ref "J1") (pin "1") (pinfunction "1_1") (pintype "passive"))
      (node (ref "J2") (pin "2") (pinfunction "2_2") (pintype "bidirectional"))
      (node (ref "J3") (pin "2") (pinfunction "2_2") (pintype "bidirectional"))
      (node (ref "J4") (pin "2") (pinfunction "2_2") (pintype "bidirectional"))
      (node (ref "J5") (pin "2") (pinfunction "2_2") (pintype "bidirectional"))
      (node (ref "R10") (pin "2") (pinfunction "2_2") (pintype "passive"))
      (node (ref "R16") (pin "1") (pinfunction "1_1") (pintype "passive"))
      (node (ref "R6") (pin "2") (pinfunction "2_2") (pintype "passive"))
      (node (ref "R8") (pin "2") (pinfunction "2_2") (pintype "passive"))
      (node (ref "RJ11_1") (pin "P$3") (pinfunction "3_P$3") (pintype "bidirectional"))
      (node (ref "RJ11_2") (pin "P$3") (pinfunction "3_P$3") (pintype "bidirectional"))
      (node (ref "U$1") (pin "GND") (pinfunction "GND_GND") (pintype "bidirectional"))
      (node (ref "U$1") (pin "GND3") (pinfunction "GND2_GND3") (pintype "bidirectional"))
      (node (ref "U$2") (pin "IN-") (pinfunction "IN-_IN-") (pintype "bidirectional"))
      (node (ref "U$2") (pin "OUT-") (pinfunction "OUT-_OUT-") (pintype "bidirectional"))
      (node (ref "VPV") (pin "2") (pinfunction "2_2") (pintype "bidirectional"))
    )
    (net (code "18") (name "I2C_SCL") (class "Default")
      (node (ref "IC2") (pin "5") (pinfunction "SCL_5") (pintype "bidirectional"))
      (node (ref "IC5") (pin "10") (pinfunction "SCL_10") (pintype "bidirectional"))
      (node (ref "R2") (pin "1") (pinfunction "1_1") (pintype "passive"))
      (node (ref "U$1") (pin "21") (pinfunction "21_21") (pintype "bidirectional"))
    )
    (net (code "19") (name "I2C_SDA") (class "Default")
      (node (ref "IC2") (pin "4") (pinfunction "SDA_4") (pintype "bidirectional"))
      (node (ref "IC5") (pin "9") (pinfunction "SDA_9") (pintype "bidirectional"))
      (node (ref "R1") (pin "1") (pinfunction "1_1") (pintype "passive"))
      (node (ref "U$1") (pin "22") (pinfunction "22_22") (pintype "bidirectional"))
    )
    (net (code "20") (name "MSHUNT_ADC") (class "Default")
      (node (ref "C5") (pin "1") (pinfunction "1_1") (pintype "passive"))
      (node (ref "IC2") (pin "3") (pinfunction "AIN_3") (pintype "bidirectional"))
      (node (ref "R3") (pin "1") (pinfunction "1_1") (pintype "passive"))
    )
    (net (code "21") (name "MSHUNT_AMP") (class "Default")
      (node (ref "IC1") (pin "5") (pinfunction "OUT_5") (pintype "bidirectional"))
      (node (ref "R3") (pin "2") (pinfunction "2_2") (pintype "passive"))
    )
    (net (code "22") (name "MSHUNT_B") (class "Default")
      (node (ref "IC1") (pin "8") (pinfunction "IN+_8") (pintype "bidirectional"))
      (node (ref "MSHUNT") (pin "1") (pinfunction "1_1") (pintype "bidirectional"))
    )
    (net (code "23") (name "MSHUNT_M") (class "Default")
      (node (ref "IC1") (pin "1") (pinfunction "IN-_1") (pintype "bidirectional"))
      (node (ref "MSHUNT") (pin "2") (pinfunction "2_2") (pintype "bidirectional"))
    )
    (net (code "24") (name "N$4") (class "Default")
      (node (ref "U$1") (pin "14") (pinfunction "14_14") (pintype "bidirectional"))
    )
    (net (code "25") (name "N$13") (class "Default")
      (node (ref "U$1") (pin "2") (pinfunction "2_2") (pintype "bidirectional"))
    )
    (net (code "26") (name "N$23") (class "Default")
      (node (ref "U$1") (pin "GND1") (pinfunction "GND1_GND1") (pintype "bidirectional"))
    )
    (net (code "27") (name "N$27") (class "Default")
      (node (ref "U$1") (pin "LORA2") (pinfunction "LORA2_LORA2") (pintype "bidirectional"))
    )
    (net (code "28") (name "N$28") (class "Default")
      (node (ref "U$1") (pin "LORA1") (pinfunction "LORA1_LORA1") (pintype "bidirectional"))
    )
    (net (code "29") (name "Net-(IC6-VOUT)") (class "Default")
      (node (ref "IC6") (pin "7") (pinfunction "VOUT_7") (pintype "output"))
      (node (ref "R15") (pin "1") (pinfunction "1_1") (pintype "passive"))
    )
    (net (code "30") (name "Net-(IC6-~{FAULT})") (class "Default")
      (node (ref "IC6") (pin "6") (pinfunction "~{FAULT}_6") (pintype "bidirectional"))
      (node (ref "R11") (pin "2") (pinfunction "2_2") (pintype "passive"))
    )
    (net (code "31") (name "Net-(IC8-VOUT)") (class "Default")
      (node (ref "IC8") (pin "3") (pinfunction "VOUT_3") (pintype "bidirectional"))
      (node (ref "R17") (pin "1") (pinfunction "1_1") (pintype "passive"))
    )
    (net (code "32") (name "PV_AIN1") (class "Default")
      (node (ref "C12") (pin "1") (pinfunction "1_1") (pintype "passive"))
      (node (ref "IC5") (pin "5") (pinfunction "AIN1_5") (pintype "bidirectional"))
      (node (ref "R7") (pin "2") (pinfunction "2_2") (pintype "passive"))
      (node (ref "R8") (pin "1") (pinfunction "1_1") (pintype "passive"))
    )
    (net (code "33") (name "RS485_A") (class "Default")
      (node (ref "D1") (pin "1") (pinfunction "1_1") (pintype "bidirectional"))
      (node (ref "IC7") (pin "6") (pinfunction "A_6") (pintype "bidirectional"))
      (node (ref "J5") (pin "3") (pinfunction "3_3") (pintype "bidirectional"))
      (node (ref "R14") (pin "1") (pinfunction "1_1") (pintype "passive"))
      (node (ref "RJ11_1") (pin "P$2") (pinfunction "2_P$2") (pintype "bidirectional"))
      (node (ref "RJ11_2") (pin "P$2") (pinfunction "2_P$2") (pintype "bidirectional"))
    )
    (net (code "34") (name "RS485_B") (class "Default")
      (node (ref "D2") (pin "1") (pinfunction "1_1") (pintype "bidirectional"))
      (node (ref "IC7") (pin "7") (pinfunction "B_7") (pintype "bidirectional"))
      (node (ref "J5") (pin "4") (pinfunction "4_4") (pintype "bidirectional"))
      (node (ref "R14") (pin "2") (pinfunction "2_2") (pintype "passive"))
      (node (ref "RJ11_1") (pin "P$4") (pinfunction "4_P$4") (pintype "bidirectional"))
      (node (ref "RJ11_2") (pin "P$4") (pinfunction "4_P$4") (pintype "bidirectional"))
    )
    (net (code "35") (name "RST") (class "Default")
      (node (ref "U$1") (pin "RST") (pinfunction "RST_RST") (pintype "bidirectional"))
    )
    (net (code "36") (name "TEMP1") (class "Default")
      (node (ref "C18") (pin "1") (pinfunction "1_1") (pintype "passive"))
      (node (ref "R17") (pin "2") (pinfunction "2_2") (pintype "passive"))
      (node (ref "U$1") (pin "13") (pinfunction "13_13") (pintype "bidirectional"))
    )
    (net (code "37") (name "TXEN") (class "Default")
      (node (ref "IC7") (pin "3") (pinfunction "DE_3") (pintype "bidirectional"))
      (node (ref "R16") (pin "2") (pinfunction "2_2") (pintype "passive"))
      (node (ref "U$1") (pin "4") (pinfunction "4_4") (pintype "bidirectional"))
    )
    (net (code "38") (name "UART_RX") (class "Default")
      (node (ref "IC7") (pin "1") (pinfunction "R_1") (pintype "bidirectional"))
      (node (ref "R13") (pin "1") (pinfunction "1_1") (pintype "passive"))
      (node (ref "U$1") (pin "RX") (pinfunction "RX_RX") (pintype "bidirectional"))
    )
    (net (code "39") (name "UART_TX") (class "Default")
      (node (ref "IC7") (pin "4") (pinfunction "D_4") (pintype "bidirectional"))
      (node (ref "U$1") (pin "TX") (pinfunction "TX_TX") (pintype "bidirectional"))
    )
    (net (code "40") (name "VCC_3V3") (class "Default")
      (node (ref "C1") (pin "1") (pinfunction "1_1") (pintype "passive"))
      (node (ref "C10") (pin "1") (pinfunction "1_1") (pintype "passive"))
      (node (ref "C14") (pin "1") (pinfunction "1_1") (pintype "passive"))
      (node (ref "C16") (pin "1") (pinfunction "1_1") (pintype "passive"))
      (node (ref "C17") (pin "1") (pinfunction "1_1") (pintype "passive"))
      (node (ref "C2") (pin "1") (pinfunction "1_1") (pintype "passive"))
      (node (ref "C3") (pin "1") (pinfunction "1_1") (pintype "passive"))
      (node (ref "C4") (pin "1") (pinfunction "1_1") (pintype "passive"))
      (node (ref "C6") (pin "1") (pinfunction "1_1") (pintype "passive"))
      (node (ref "C8") (pin "1") (pinfunction "1_1") (pintype "passive"))
      (node (ref "IC1") (pin "3") (pinfunction "REF2_3") (pintype "bidirectional"))
      (node (ref "IC1") (pin "6") (pinfunction "VS_6") (pintype "bidirectional"))
      (node (ref "IC2") (pin "1") (pinfunction "VDD_1") (pintype "bidirectional"))
      (node (ref "IC3") (pin "2") (pinfunction "OUTPUT_2") (pintype "bidirectional"))
      (node (ref "IC3") (pin "4") (pinfunction "VOUT_4") (pintype "bidirectional"))
      (node (ref "IC4") (pin "1") (pinfunction "VCC_1") (pintype "power_in"))
      (node (ref "IC5") (pin "8") (pinfunction "VDD_8") (pintype "bidirectional"))
      (node (ref "IC6") (pin "8") (pinfunction "VCC_8") (pintype "power_in"))
      (node (ref "IC7") (pin "8") (pinfunction "VCC_8") (pintype "bidirectional"))
      (node (ref "IC8") (pin "4") (pinfunction "VDD_4") (pintype "bidirectional"))
      (node (ref "R1") (pin "2") (pinfunction "2_2") (pintype "passive"))
      (node (ref "R11") (pin "1") (pinfunction "1_1") (pintype "passive"))
      (node (ref "R12") (pin "2") (pinfunction "2_2") (pintype "passive"))
      (node (ref "R13") (pin "2") (pinfunction "2_2") (pintype "passive"))
      (node (ref "R2") (pin "2") (pinfunction "2_2") (pintype "passive"))
      (node (ref "RJ11_1") (pin "P$1") (pinfunction "1_P$1") (pintype "bidirectional"))
      (node (ref "RJ11_2") (pin "P$1") (pinfunction "1_P$1") (pintype "bidirectional"))
      (node (ref "U$1") (pin "3.3V") (pinfunction "3.3V_3.3V") (pintype "bidirectional"))
      (node (ref "U$1") (pin "3V3") (pinfunction "3V3_3V3") (pintype "bidirectional"))
    )
    (net (code "41") (name "VCC_5V") (class "Default")
      (node (ref "C7") (pin "1") (pinfunction "1_1") (pintype "passive"))
      (node (ref "IC3") (pin "3") (pinfunction "INPUT_3") (pintype "bidirectional"))
      (node (ref "J2") (pin "1") (pinfunction "1_1") (pintype "bidirectional"))
      (node (ref "J3") (pin "1") (pinfunction "1_1") (pintype "bidirectional"))
      (node (ref "J4") (pin "1") (pinfunction "1_1") (pintype "bidirectional"))
      (node (ref "J5") (pin "1") (pinfunction "1_1") (pintype "bidirectional"))
      (node (ref "U$1") (pin "5V") (pinfunction "5V_5V") (pintype "bidirectional"))
      (node (ref "U$2") (pin "OUT+") (pinfunction "OUT+_OUT+") (pintype "bidirectional"))
    )
    (net (code "42") (name "VCC_12V") (class "Default")
      (node (ref "IC6") (pin "3") (pinfunction "IP-_3") (pintype "passive"))
      (node (ref "IC6") (pin "4") (pinfunction "IP-1_4") (pintype "passive"))
      (node (ref "J1") (pin "2") (pinfunction "2_2") (pintype "passive"))
      (node (ref "R9") (pin "1") (pinfunction "1_1") (pintype "passive"))
      (node (ref "U$2") (pin "IN+") (pinfunction "IN+_IN+") (pintype "bidirectional"))
    )
    (net (code "43") (name "VCC_BBANK") (class "Default")
      (node (ref "BBANK") (pin "1") (pinfunction "1_1") (pintype "bidirectional"))
      (node (ref "R5") (pin "1") (pinfunction "1_1") (pintype "passive"))
    )
    (net (code "44") (name "VCC_PV") (class "Default")
      (node (ref "R7") (pin "1") (pinfunction "1_1") (pintype "passive"))
      (node (ref "VPV") (pin "1") (pinfunction "1_1") (pintype "bidirectional"))
    )
    (net (code "45") (name "unconnected-(IC1-NC-Pad4)") (class "Default")
      (node (ref "IC1") (pin "4") (pinfunction "NC_4") (pintype "no_connect"))
    )
    (net (code "46") (name "unconnected-(IC5-ALERT{slash}RDY-Pad2)") (class "Default")
      (node (ref "IC5") (pin "2") (pinfunction "ALERT/RDY_2") (pintype "bidirectional"))
    )
    (net (code "47") (name "unconnected-(IC8-NC_1-Pad1)") (class "Default")
      (node (ref "IC8") (pin "1") (pinfunction "NC_1_1") (pintype "bidirectional"))
    )
    (net (code "48") (name "unconnected-(IC8-NC_2-Pad5)") (class "Default")
      (node (ref "IC8") (pin "5") (pinfunction "NC_2_5") (pintype "bidirectional"))
    )
    (net (code "49") (name "~{RXEN}") (class "Default")
      (node (ref "IC7") (pin "2") (pinfunction "~{RE}_2") (pintype "bidirectional"))
      (node (ref "R12") (pin "1") (pinfunction "1_1") (pintype "passive"))
      (node (ref "U$1") (pin "23") (pinfunction "23_23") (pintype "bidirectional"))
    )
  )
)
